# RPi-FabScan-HAT_v12.net
KiCad netlist of a schematic drawn in EAGLE
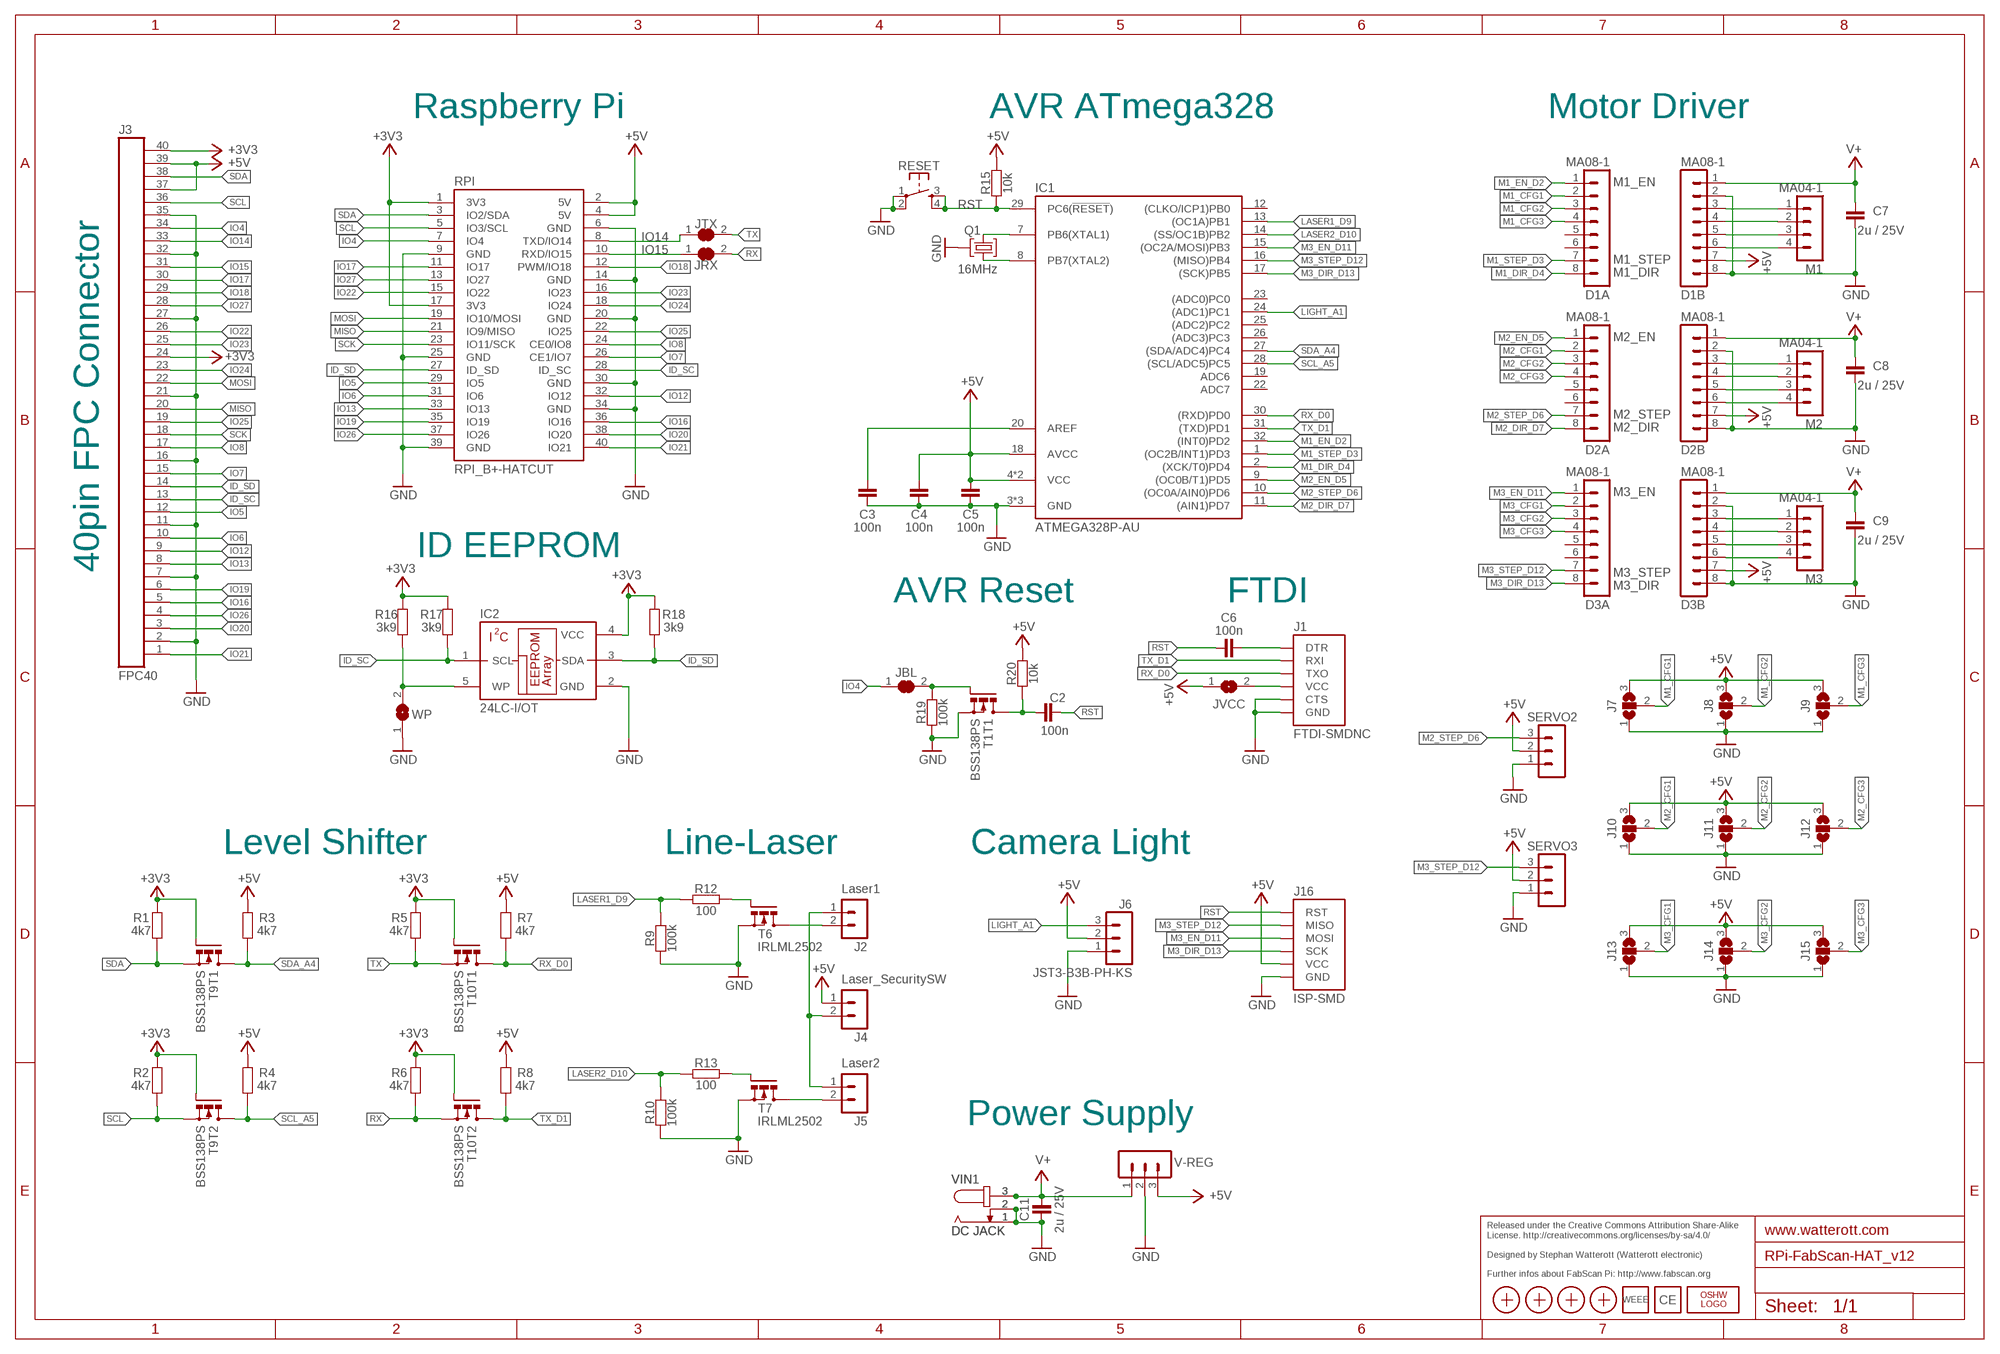
[diagram p0: schematic, sheet 1]

(export (version "E")
  (design (tool "Eeschema 10.0.6"))
  (components
    (comp (ref "1")
      (value "PASSER-07")
      (footprint "eagle-import:PASSER_07MM")
      (libsource (lib "eagle-import") (part "PASSER-07"))
    )
    (comp (ref "2")
      (value "PASSER-07")
      (footprint "eagle-import:PASSER_07MM")
      (libsource (lib "eagle-import") (part "PASSER-07"))
    )
    (comp (ref "C2")
      (value "100n")
      (footprint "eagle-import:C0402")
      (libsource (lib "eagle-import") (part "CAPACITOR-0402"))
    )
    (comp (ref "C3")
      (value "100n")
      (footprint "eagle-import:C0402")
      (libsource (lib "eagle-import") (part "CAPACITOR-0402"))
    )
    (comp (ref "C4")
      (value "100n")
      (footprint "eagle-import:C0402")
      (libsource (lib "eagle-import") (part "CAPACITOR-0402"))
    )
    (comp (ref "C5")
      (value "100n")
      (footprint "eagle-import:C0402")
      (libsource (lib "eagle-import") (part "CAPACITOR-0402"))
    )
    (comp (ref "C6")
      (value "100n")
      (footprint "eagle-import:C0402")
      (libsource (lib "eagle-import") (part "CAPACITOR-0402"))
    )
    (comp (ref "C7")
      (value "2u / 25V")
      (footprint "eagle-import:C1206")
      (libsource (lib "eagle-import") (part "CAPACITOR-1206"))
    )
    (comp (ref "C8")
      (value "2u / 25V")
      (footprint "eagle-import:C1206")
      (libsource (lib "eagle-import") (part "CAPACITOR-1206"))
    )
    (comp (ref "C9")
      (value "2u / 25V")
      (footprint "eagle-import:C1206")
      (libsource (lib "eagle-import") (part "CAPACITOR-1206"))
    )
    (comp (ref "C11")
      (value "2u / 25V")
      (footprint "eagle-import:C1206")
      (libsource (lib "eagle-import") (part "CAPACITOR-1206"))
    )
    (comp (ref "D1A")
      (value "MA08-1")
      (footprint "eagle-import:MA08-1")
      (libsource (lib "eagle-import") (part "MA08-1"))
    )
    (comp (ref "D1B")
      (value "MA08-1")
      (footprint "eagle-import:MA08-1")
      (libsource (lib "eagle-import") (part "MA08-1"))
    )
    (comp (ref "D2A")
      (value "MA08-1")
      (footprint "eagle-import:MA08-1")
      (libsource (lib "eagle-import") (part "MA08-1"))
    )
    (comp (ref "D2B")
      (value "MA08-1")
      (footprint "eagle-import:MA08-1")
      (libsource (lib "eagle-import") (part "MA08-1"))
    )
    (comp (ref "D3A")
      (value "MA08-1")
      (footprint "eagle-import:MA08-1")
      (libsource (lib "eagle-import") (part "MA08-1"))
    )
    (comp (ref "D3B")
      (value "MA08-1")
      (footprint "eagle-import:MA08-1")
      (libsource (lib "eagle-import") (part "MA08-1"))
    )
    (comp (ref "IC1")
      (value "ATMEGA328P-AU")
      (footprint "eagle-import:TQFP32")
      (libsource (lib "eagle-import") (part "ATMEGA328P-AU"))
    )
    (comp (ref "IC2")
      (value "24LC-I/OT")
      (footprint "eagle-import:SOT23-5")
      (libsource (lib "eagle-import") (part "24LC-I/OT"))
    )
    (comp (ref "J1")
      (value "FTDI-SMDNC")
      (footprint "eagle-import:FTDI_SMDNC")
      (libsource (lib "eagle-import") (part "FTDI-SMDNC"))
    )
    (comp (ref "J2")
      (value "Laser1")
      (footprint "eagle-import:MA02-1")
      (libsource (lib "eagle-import") (part "MA02-1"))
    )
    (comp (ref "J3")
      (value "FPC40")
      (footprint "eagle-import:FPC40-0.5")
      (libsource (lib "eagle-import") (part "FPC40"))
    )
    (comp (ref "J4")
      (value "Laser_SecuritySW")
      (footprint "eagle-import:MA02-1")
      (libsource (lib "eagle-import") (part "MA02-1"))
    )
    (comp (ref "J5")
      (value "Laser2")
      (footprint "eagle-import:MA02-1")
      (libsource (lib "eagle-import") (part "MA02-1"))
    )
    (comp (ref "J6")
      (value "JST3-B3B-PH-KS")
      (footprint "eagle-import:JST_B3B-PH-KS")
      (libsource (lib "eagle-import") (part "JST3-B3B-PH-KS"))
    )
    (comp (ref "J7")
      (value "JUMPER3-0603-NC")
      (footprint "eagle-import:JUMPER3-0603_NC")
      (libsource (lib "eagle-import") (part "JUMPER3-0603-NC"))
    )
    (comp (ref "J8")
      (value "JUMPER3-0603-NC")
      (footprint "eagle-import:JUMPER3-0603_NC")
      (libsource (lib "eagle-import") (part "JUMPER3-0603-NC"))
    )
    (comp (ref "J9")
      (value "JUMPER3-0603-NC")
      (footprint "eagle-import:JUMPER3-0603_NC")
      (libsource (lib "eagle-import") (part "JUMPER3-0603-NC"))
    )
    (comp (ref "J10")
      (value "JUMPER3-0603-NC")
      (footprint "eagle-import:JUMPER3-0603_NC")
      (libsource (lib "eagle-import") (part "JUMPER3-0603-NC"))
    )
    (comp (ref "J11")
      (value "JUMPER3-0603-NC")
      (footprint "eagle-import:JUMPER3-0603_NC")
      (libsource (lib "eagle-import") (part "JUMPER3-0603-NC"))
    )
    (comp (ref "J12")
      (value "JUMPER3-0603-NC")
      (footprint "eagle-import:JUMPER3-0603_NC")
      (libsource (lib "eagle-import") (part "JUMPER3-0603-NC"))
    )
    (comp (ref "J13")
      (value "JUMPER3-0603-NC")
      (footprint "eagle-import:JUMPER3-0603_NC")
      (libsource (lib "eagle-import") (part "JUMPER3-0603-NC"))
    )
    (comp (ref "J14")
      (value "JUMPER3-0603-NC")
      (footprint "eagle-import:JUMPER3-0603_NC")
      (libsource (lib "eagle-import") (part "JUMPER3-0603-NC"))
    )
    (comp (ref "J15")
      (value "JUMPER3-0603-NC")
      (footprint "eagle-import:JUMPER3-0603_NC")
      (libsource (lib "eagle-import") (part "JUMPER3-0603-NC"))
    )
    (comp (ref "J16")
      (value "ISP-SMD")
      (footprint "eagle-import:ISP-2X3_SMD")
      (libsource (lib "eagle-import") (part "ISP-SMD"))
    )
    (comp (ref "JBL")
      (value "JUMPER2-0402-NC")
      (footprint "eagle-import:JUMPER2-0402_NC")
      (libsource (lib "eagle-import") (part "JUMPER2-0402-NC"))
    )
    (comp (ref "JRX")
      (value "JUMPER2-0402-NC")
      (footprint "eagle-import:JUMPER2-0402_NC")
      (libsource (lib "eagle-import") (part "JUMPER2-0402-NC"))
    )
    (comp (ref "JTX")
      (value "JUMPER2-0402-NC")
      (footprint "eagle-import:JUMPER2-0402_NC")
      (libsource (lib "eagle-import") (part "JUMPER2-0402-NC"))
    )
    (comp (ref "JVCC")
      (value "JUMPER2-0402-NC")
      (footprint "eagle-import:JUMPER2-0402_NC")
      (libsource (lib "eagle-import") (part "JUMPER2-0402-NC"))
    )
    (comp (ref "LOGO1")
      (value "LOGO_CE-2")
      (footprint "eagle-import:CE_2MM")
      (libsource (lib "eagle-import") (part "LOGO_CE-2"))
    )
    (comp (ref "LOGO2")
      (value "OSHW_LOGOX0100")
      (footprint "eagle-import:OSHW_6X100")
      (libsource (lib "eagle-import") (part "OSHW_LOGOX0100"))
    )
    (comp (ref "LOGO3")
      (value "LOGO_WEEE-4")
      (footprint "eagle-import:WEEE_4MM")
      (libsource (lib "eagle-import") (part "LOGO_WEEE-4"))
    )
    (comp (ref "M1")
      (value "MA04-1")
      (footprint "eagle-import:MA04-1")
      (libsource (lib "eagle-import") (part "MA04-1"))
    )
    (comp (ref "M2")
      (value "MA04-1")
      (footprint "eagle-import:MA04-1")
      (libsource (lib "eagle-import") (part "MA04-1"))
    )
    (comp (ref "M3")
      (value "MA04-1")
      (footprint "eagle-import:MA04-1")
      (libsource (lib "eagle-import") (part "MA04-1"))
    )
    (comp (ref "Q1")
      (value "16MHz")
      (footprint "eagle-import:CRYSTAL_32X13")
      (libsource (lib "eagle-import") (part "CRYSTAL-RES-32"))
    )
    (comp (ref "R1")
      (value "4k7")
      (footprint "eagle-import:C0402")
      (libsource (lib "eagle-import") (part "RESISTOR-0402"))
    )
    (comp (ref "R2")
      (value "4k7")
      (footprint "eagle-import:C0402")
      (libsource (lib "eagle-import") (part "RESISTOR-0402"))
    )
    (comp (ref "R3")
      (value "4k7")
      (footprint "eagle-import:C0402")
      (libsource (lib "eagle-import") (part "RESISTOR-0402"))
    )
    (comp (ref "R4")
      (value "4k7")
      (footprint "eagle-import:C0402")
      (libsource (lib "eagle-import") (part "RESISTOR-0402"))
    )
    (comp (ref "R5")
      (value "4k7")
      (footprint "eagle-import:C0402")
      (libsource (lib "eagle-import") (part "RESISTOR-0402"))
    )
    (comp (ref "R6")
      (value "4k7")
      (footprint "eagle-import:C0402")
      (libsource (lib "eagle-import") (part "RESISTOR-0402"))
    )
    (comp (ref "R7")
      (value "4k7")
      (footprint "eagle-import:C0402")
      (libsource (lib "eagle-import") (part "RESISTOR-0402"))
    )
    (comp (ref "R8")
      (value "4k7")
      (footprint "eagle-import:C0402")
      (libsource (lib "eagle-import") (part "RESISTOR-0402"))
    )
    (comp (ref "R9")
      (value "100k")
      (footprint "eagle-import:C0402")
      (libsource (lib "eagle-import") (part "RESISTOR-0402"))
    )
    (comp (ref "R10")
      (value "100k")
      (footprint "eagle-import:C0402")
      (libsource (lib "eagle-import") (part "RESISTOR-0402"))
    )
    (comp (ref "R12")
      (value "100")
      (footprint "eagle-import:C0402")
      (libsource (lib "eagle-import") (part "RESISTOR-0402"))
    )
    (comp (ref "R13")
      (value "100")
      (footprint "eagle-import:C0402")
      (libsource (lib "eagle-import") (part "RESISTOR-0402"))
    )
    (comp (ref "R15")
      (value "10k")
      (footprint "eagle-import:C0402")
      (libsource (lib "eagle-import") (part "RESISTOR-0402"))
    )
    (comp (ref "R16")
      (value "3k9")
      (footprint "eagle-import:C0402")
      (libsource (lib "eagle-import") (part "RESISTOR-0402"))
    )
    (comp (ref "R17")
      (value "3k9")
      (footprint "eagle-import:C0402")
      (libsource (lib "eagle-import") (part "RESISTOR-0402"))
    )
    (comp (ref "R18")
      (value "3k9")
      (footprint "eagle-import:C0402")
      (libsource (lib "eagle-import") (part "RESISTOR-0402"))
    )
    (comp (ref "R19")
      (value "100k")
      (footprint "eagle-import:C0402")
      (libsource (lib "eagle-import") (part "RESISTOR-0402"))
    )
    (comp (ref "R20")
      (value "10k")
      (footprint "eagle-import:C0402")
      (libsource (lib "eagle-import") (part "RESISTOR-0402"))
    )
    (comp (ref "RESET")
      (value "SW-TACTILE-PTS840P")
      (footprint "eagle-import:SW_PTS840P")
      (libsource (lib "eagle-import") (part "SW-TACTILE-PTS840P"))
    )
    (comp (ref "RPI")
      (value "RPI_B+-HATCUT")
      (footprint "eagle-import:RPI-B+HAT_CUTOUT")
      (libsource (lib "eagle-import") (part "RPI_B+-HATCUT"))
    )
    (comp (ref "SERVO2")
      (value "MA03-1")
      (footprint "eagle-import:MA03-1")
      (libsource (lib "eagle-import") (part "MA03-1"))
    )
    (comp (ref "SERVO3")
      (value "MA03-1")
      (footprint "eagle-import:MA03-1")
      (libsource (lib "eagle-import") (part "MA03-1"))
    )
    (comp (ref "T1")
      (value "BSS138PS")
      (footprint "eagle-import:SOT363")
      (libsource (lib "eagle-import") (part "BSS138PS"))
    )
    (comp (ref "T6")
      (value "IRLML2502")
      (footprint "eagle-import:SOT23")
      (libsource (lib "eagle-import") (part "MOSFET-N-SOT23"))
    )
    (comp (ref "T7")
      (value "IRLML2502")
      (footprint "eagle-import:SOT23")
      (libsource (lib "eagle-import") (part "MOSFET-N-SOT23"))
    )
    (comp (ref "T9")
      (value "BSS138PS")
      (footprint "eagle-import:SOT363")
      (libsource (lib "eagle-import") (part "BSS138PS"))
    )
    (comp (ref "T10")
      (value "BSS138PS")
      (footprint "eagle-import:SOT363")
      (libsource (lib "eagle-import") (part "BSS138PS"))
    )
    (comp (ref "V-REG")
      (value "MA03-1")
      (footprint "eagle-import:MA03-1")
      (libsource (lib "eagle-import") (part "MA03-1"))
    )
    (comp (ref "VIN")
      (value "DC JACK")
      (footprint "eagle-import:DC-JACK")
      (libsource (lib "eagle-import") (part "DC-JACK-2.1"))
    )
    (comp (ref "VIN1")
      (value "DC JACK")
      (footprint "eagle-import:DC-JACK")
      (libsource (lib "eagle-import") (part "DC-JACK-2.1"))
    )
    (comp (ref "WP")
      (value "JUMPER2-0402-NC")
      (footprint "eagle-import:JUMPER2-0402_NC")
      (libsource (lib "eagle-import") (part "JUMPER2-0402-NC"))
    )
    (comp (ref "X1")
      (value "PASSER-07")
      (footprint "eagle-import:PASSER_07MM")
      (libsource (lib "eagle-import") (part "PASSER-07"))
    )
    (comp (ref "X4")
      (value "PASSER-07")
      (footprint "eagle-import:PASSER_07MM")
      (libsource (lib "eagle-import") (part "PASSER-07"))
    )
  )
  (nets
    (net (code "1") (name "+3V3") (class "Default")
      (node (ref "IC2") (pin "4") (pinfunction "VCC_4") (pintype "power_in"))
      (node (ref "J3") (pin "24") (pinfunction "24_24") (pintype "passive"))
      (node (ref "J3") (pin "40") (pinfunction "40_40") (pintype "passive"))
      (node (ref "R1") (pin "1") (pinfunction "1_1") (pintype "passive"))
      (node (ref "R16") (pin "2") (pinfunction "2_2") (pintype "passive"))
      (node (ref "R17") (pin "2") (pinfunction "2_2") (pintype "passive"))
      (node (ref "R18") (pin "2") (pinfunction "2_2") (pintype "passive"))
      (node (ref "R2") (pin "1") (pinfunction "1_1") (pintype "passive"))
      (node (ref "R5") (pin "1") (pinfunction "1_1") (pintype "passive"))
      (node (ref "R6") (pin "1") (pinfunction "1_1") (pintype "passive"))
      (node (ref "RPI") (pin "1") (pinfunction "3V3_1") (pintype "passive"))
      (node (ref "RPI") (pin "17") (pinfunction "3V3_17") (pintype "passive"))
      (node (ref "T10") (pin "2") (pinfunction "G_2") (pintype "passive"))
      (node (ref "T10") (pin "5") (pinfunction "G_5") (pintype "passive"))
      (node (ref "T9") (pin "2") (pinfunction "G_2") (pintype "passive"))
      (node (ref "T9") (pin "5") (pinfunction "G_5") (pintype "passive"))
    )
    (net (code "2") (name "+5V") (class "Default")
      (node (ref "C4") (pin "2") (pinfunction "2_2") (pintype "passive"))
      (node (ref "C5") (pin "2") (pinfunction "2_2") (pintype "passive"))
      (node (ref "D1B") (pin "7") (pinfunction "7_7") (pintype "passive"))
      (node (ref "D2B") (pin "7") (pinfunction "7_7") (pintype "passive"))
      (node (ref "D3B") (pin "7") (pinfunction "7_7") (pintype "passive"))
      (node (ref "IC1") (pin "18") (pinfunction "AVCC_18") (pintype "power_in"))
      (node (ref "IC1") (pin "4") (pinfunction "VCC_4") (pintype "power_in"))
      (node (ref "IC1") (pin "6") (pinfunction "VCC_6") (pintype "power_in"))
      (node (ref "J10") (pin "3") (pinfunction "3_3") (pintype "passive"))
      (node (ref "J11") (pin "3") (pinfunction "3_3") (pintype "passive"))
      (node (ref "J12") (pin "3") (pinfunction "3_3") (pintype "passive"))
      (node (ref "J13") (pin "3") (pinfunction "3_3") (pintype "passive"))
      (node (ref "J14") (pin "3") (pinfunction "3_3") (pintype "passive"))
      (node (ref "J15") (pin "3") (pinfunction "3_3") (pintype "passive"))
      (node (ref "J16") (pin "VCC") (pinfunction "VCC_VCC") (pintype "power_in"))
      (node (ref "J3") (pin "37") (pinfunction "37_37") (pintype "passive"))
      (node (ref "J3") (pin "39") (pinfunction "39_39") (pintype "passive"))
      (node (ref "J4") (pin "1") (pinfunction "1_1") (pintype "passive"))
      (node (ref "J6") (pin "2") (pinfunction "2_2") (pintype "passive"))
      (node (ref "J7") (pin "3") (pinfunction "3_3") (pintype "passive"))
      (node (ref "J8") (pin "3") (pinfunction "3_3") (pintype "passive"))
      (node (ref "J9") (pin "3") (pinfunction "3_3") (pintype "passive"))
      (node (ref "JVCC") (pin "1") (pinfunction "1_1") (pintype "passive"))
      (node (ref "R15") (pin "2") (pinfunction "2_2") (pintype "passive"))
      (node (ref "R20") (pin "2") (pinfunction "2_2") (pintype "passive"))
      (node (ref "R3") (pin "1") (pinfunction "1_1") (pintype "passive"))
      (node (ref "R4") (pin "1") (pinfunction "1_1") (pintype "passive"))
      (node (ref "R7") (pin "1") (pinfunction "1_1") (pintype "passive"))
      (node (ref "R8") (pin "1") (pinfunction "1_1") (pintype "passive"))
      (node (ref "RPI") (pin "2") (pinfunction "5V_2") (pintype "passive"))
      (node (ref "RPI") (pin "4") (pinfunction "5V_4") (pintype "passive"))
      (node (ref "SERVO2") (pin "2") (pinfunction "2_2") (pintype "passive"))
      (node (ref "SERVO3") (pin "2") (pinfunction "2_2") (pintype "passive"))
      (node (ref "V-REG") (pin "3") (pinfunction "3_3") (pintype "passive"))
    )
    (net (code "3") (name "GND") (class "Default")
      (node (ref "C11") (pin "1") (pinfunction "1_1") (pintype "passive"))
      (node (ref "C3") (pin "1") (pinfunction "1_1") (pintype "passive"))
      (node (ref "C4") (pin "1") (pinfunction "1_1") (pintype "passive"))
      (node (ref "C5") (pin "1") (pinfunction "1_1") (pintype "passive"))
      (node (ref "C7") (pin "1") (pinfunction "1_1") (pintype "passive"))
      (node (ref "C8") (pin "1") (pinfunction "1_1") (pintype "passive"))
      (node (ref "C9") (pin "1") (pinfunction "1_1") (pintype "passive"))
      (node (ref "D1B") (pin "2") (pinfunction "2_2") (pintype "passive"))
      (node (ref "D1B") (pin "8") (pinfunction "8_8") (pintype "passive"))
      (node (ref "D2B") (pin "2") (pinfunction "2_2") (pintype "passive"))
      (node (ref "D2B") (pin "8") (pinfunction "8_8") (pintype "passive"))
      (node (ref "D3B") (pin "2") (pinfunction "2_2") (pintype "passive"))
      (node (ref "D3B") (pin "8") (pinfunction "8_8") (pintype "passive"))
      (node (ref "IC1") (pin "21") (pinfunction "GND_21") (pintype "power_in"))
      (node (ref "IC1") (pin "3") (pinfunction "GND_3") (pintype "power_in"))
      (node (ref "IC1") (pin "5") (pinfunction "GND_5") (pintype "power_in"))
      (node (ref "IC2") (pin "2") (pinfunction "GND_2") (pintype "power_in"))
      (node (ref "J1") (pin "1-GND") (pinfunction "GND_1-GND") (pintype "power_in"))
      (node (ref "J1") (pin "2-CTS") (pinfunction "CTS_2-CTS") (pintype "bidirectional"))
      (node (ref "J10") (pin "1") (pinfunction "1_1") (pintype "passive"))
      (node (ref "J11") (pin "1") (pinfunction "1_1") (pintype "passive"))
      (node (ref "J12") (pin "1") (pinfunction "1_1") (pintype "passive"))
      (node (ref "J13") (pin "1") (pinfunction "1_1") (pintype "passive"))
      (node (ref "J14") (pin "1") (pinfunction "1_1") (pintype "passive"))
      (node (ref "J15") (pin "1") (pinfunction "1_1") (pintype "passive"))
      (node (ref "J16") (pin "GND") (pinfunction "GND_GND") (pintype "power_in"))
      (node (ref "J3") (pin "11") (pinfunction "11_11") (pintype "passive"))
      (node (ref "J3") (pin "16") (pinfunction "16_16") (pintype "passive"))
      (node (ref "J3") (pin "2") (pinfunction "2_2") (pintype "passive"))
      (node (ref "J3") (pin "21") (pinfunction "21_21") (pintype "passive"))
      (node (ref "J3") (pin "27") (pinfunction "27_27") (pintype "passive"))
      (node (ref "J3") (pin "32") (pinfunction "32_32") (pintype "passive"))
      (node (ref "J3") (pin "35") (pinfunction "35_35") (pintype "passive"))
      (node (ref "J3") (pin "7") (pinfunction "7_7") (pintype "passive"))
      (node (ref "J6") (pin "1") (pinfunction "1_1") (pintype "passive"))
      (node (ref "J7") (pin "1") (pinfunction "1_1") (pintype "passive"))
      (node (ref "J8") (pin "1") (pinfunction "1_1") (pintype "passive"))
      (node (ref "J9") (pin "1") (pinfunction "1_1") (pintype "passive"))
      (node (ref "Q1") (pin "GND") (pinfunction "GND_GND") (pintype "passive"))
      (node (ref "R10") (pin "1") (pinfunction "1_1") (pintype "passive"))
      (node (ref "R19") (pin "1") (pinfunction "1_1") (pintype "passive"))
      (node (ref "R9") (pin "1") (pinfunction "1_1") (pintype "passive"))
      (node (ref "RESET") (pin "1") (pinfunction "P1_1") (pintype "passive"))
      (node (ref "RESET") (pin "2") (pinfunction "P2_2") (pintype "passive"))
      (node (ref "RPI") (pin "14") (pinfunction "GND_14") (pintype "passive"))
      (node (ref "RPI") (pin "20") (pinfunction "GND_20") (pintype "passive"))
      (node (ref "RPI") (pin "25") (pinfunction "GND_25") (pintype "passive"))
      (node (ref "RPI") (pin "30") (pinfunction "GND_30") (pintype "bidirectional"))
      (node (ref "RPI") (pin "34") (pinfunction "GND_34") (pintype "bidirectional"))
      (node (ref "RPI") (pin "39") (pinfunction "GND_39") (pintype "bidirectional"))
      (node (ref "RPI") (pin "6") (pinfunction "GND_6") (pintype "passive"))
      (node (ref "RPI") (pin "9") (pinfunction "GND_9") (pintype "passive"))
      (node (ref "SERVO2") (pin "1") (pinfunction "1_1") (pintype "passive"))
      (node (ref "SERVO3") (pin "1") (pinfunction "1_1") (pintype "passive"))
      (node (ref "T1") (pin "1") (pinfunction "S_1") (pintype "passive"))
      (node (ref "T6") (pin "2") (pinfunction "S_2") (pintype "passive"))
      (node (ref "T7") (pin "2") (pinfunction "S_2") (pintype "passive"))
      (node (ref "V-REG") (pin "2") (pinfunction "2_2") (pintype "passive"))
      (node (ref "VIN") (pin "1") (pinfunction "1_1") (pintype "passive"))
      (node (ref "VIN") (pin "2") (pinfunction "2_2") (pintype "passive"))
      (node (ref "VIN1") (pin "1") (pinfunction "1_1") (pintype "passive"))
      (node (ref "VIN1") (pin "2") (pinfunction "2_2") (pintype "passive"))
      (node (ref "WP") (pin "1") (pinfunction "1_1") (pintype "passive"))
    )
    (net (code "4") (name "ID_SC") (class "Default")
      (node (ref "IC2") (pin "1") (pinfunction "SCL_1") (pintype "bidirectional"))
      (node (ref "J3") (pin "13") (pinfunction "13_13") (pintype "passive"))
      (node (ref "R17") (pin "1") (pinfunction "1_1") (pintype "passive"))
      (node (ref "RPI") (pin "28") (pinfunction "ID_SC_28") (pintype "bidirectional"))
    )
    (net (code "5") (name "ID_SD") (class "Default")
      (node (ref "IC2") (pin "3") (pinfunction "SDA_3") (pintype "bidirectional"))
      (node (ref "J3") (pin "14") (pinfunction "14_14") (pintype "passive"))
      (node (ref "R18") (pin "1") (pinfunction "1_1") (pintype "passive"))
      (node (ref "RPI") (pin "27") (pinfunction "ID_SD_27") (pintype "bidirectional"))
    )
    (net (code "6") (name "IO4") (class "Default")
      (node (ref "J3") (pin "34") (pinfunction "34_34") (pintype "passive"))
      (node (ref "JBL") (pin "1") (pinfunction "1_1") (pintype "passive"))
      (node (ref "RPI") (pin "7") (pinfunction "IO4_7") (pintype "passive"))
    )
    (net (code "7") (name "IO5") (class "Default")
      (node (ref "J3") (pin "12") (pinfunction "12_12") (pintype "passive"))
      (node (ref "RPI") (pin "29") (pinfunction "IO5_29") (pintype "bidirectional"))
    )
    (net (code "8") (name "IO6") (class "Default")
      (node (ref "J3") (pin "10") (pinfunction "10_10") (pintype "passive"))
      (node (ref "RPI") (pin "31") (pinfunction "IO6_31") (pintype "bidirectional"))
    )
    (net (code "9") (name "IO7") (class "Default")
      (node (ref "J3") (pin "15") (pinfunction "15_15") (pintype "passive"))
      (node (ref "RPI") (pin "26") (pinfunction "CE1/IO7_26") (pintype "passive"))
    )
    (net (code "10") (name "IO8") (class "Default")
      (node (ref "J3") (pin "17") (pinfunction "17_17") (pintype "passive"))
      (node (ref "RPI") (pin "24") (pinfunction "CE0/IO8_24") (pintype "passive"))
    )
    (net (code "11") (name "IO12") (class "Default")
      (node (ref "J3") (pin "9") (pinfunction "9_9") (pintype "passive"))
      (node (ref "RPI") (pin "32") (pinfunction "IO12_32") (pintype "bidirectional"))
    )
    (net (code "12") (name "IO13") (class "Default")
      (node (ref "J3") (pin "8") (pinfunction "8_8") (pintype "passive"))
      (node (ref "RPI") (pin "33") (pinfunction "IO13_33") (pintype "bidirectional"))
    )
    (net (code "13") (name "IO14") (class "Default")
      (node (ref "J3") (pin "33") (pinfunction "33_33") (pintype "passive"))
      (node (ref "JTX") (pin "1") (pinfunction "1_1") (pintype "passive"))
      (node (ref "RPI") (pin "8") (pinfunction "TXD/IO14_8") (pintype "passive"))
    )
    (net (code "14") (name "IO15") (class "Default")
      (node (ref "J3") (pin "31") (pinfunction "31_31") (pintype "passive"))
      (node (ref "JRX") (pin "1") (pinfunction "1_1") (pintype "passive"))
      (node (ref "RPI") (pin "10") (pinfunction "RXD/IO15_10") (pintype "passive"))
    )
    (net (code "15") (name "IO16") (class "Default")
      (node (ref "J3") (pin "5") (pinfunction "5_5") (pintype "passive"))
      (node (ref "RPI") (pin "36") (pinfunction "IO16_36") (pintype "bidirectional"))
    )
    (net (code "16") (name "IO17") (class "Default")
      (node (ref "J3") (pin "30") (pinfunction "30_30") (pintype "passive"))
      (node (ref "RPI") (pin "11") (pinfunction "IO17_11") (pintype "passive"))
    )
    (net (code "17") (name "IO18") (class "Default")
      (node (ref "J3") (pin "29") (pinfunction "29_29") (pintype "passive"))
      (node (ref "RPI") (pin "12") (pinfunction "PWM/IO18_12") (pintype "passive"))
    )
    (net (code "18") (name "IO19") (class "Default")
      (node (ref "J3") (pin "6") (pinfunction "6_6") (pintype "passive"))
      (node (ref "RPI") (pin "35") (pinfunction "IO19_35") (pintype "bidirectional"))
    )
    (net (code "19") (name "IO20") (class "Default")
      (node (ref "J3") (pin "3") (pinfunction "3_3") (pintype "passive"))
      (node (ref "RPI") (pin "38") (pinfunction "IO20_38") (pintype "bidirectional"))
    )
    (net (code "20") (name "IO21") (class "Default")
      (node (ref "J3") (pin "1") (pinfunction "1_1") (pintype "passive"))
      (node (ref "RPI") (pin "40") (pinfunction "IO21_40") (pintype "bidirectional"))
    )
    (net (code "21") (name "IO22") (class "Default")
      (node (ref "J3") (pin "26") (pinfunction "26_26") (pintype "passive"))
      (node (ref "RPI") (pin "15") (pinfunction "IO22_15") (pintype "passive"))
    )
    (net (code "22") (name "IO23") (class "Default")
      (node (ref "J3") (pin "25") (pinfunction "25_25") (pintype "passive"))
      (node (ref "RPI") (pin "16") (pinfunction "IO23_16") (pintype "passive"))
    )
    (net (code "23") (name "IO24") (class "Default")
      (node (ref "J3") (pin "23") (pinfunction "23_23") (pintype "passive"))
      (node (ref "RPI") (pin "18") (pinfunction "IO24_18") (pintype "passive"))
    )
    (net (code "24") (name "IO25") (class "Default")
      (node (ref "J3") (pin "19") (pinfunction "19_19") (pintype "passive"))
      (node (ref "RPI") (pin "22") (pinfunction "IO25_22") (pintype "passive"))
    )
    (net (code "25") (name "IO26") (class "Default")
      (node (ref "J3") (pin "4") (pinfunction "4_4") (pintype "passive"))
      (node (ref "RPI") (pin "37") (pinfunction "IO26_37") (pintype "bidirectional"))
    )
    (net (code "26") (name "IO27") (class "Default")
      (node (ref "J3") (pin "28") (pinfunction "28_28") (pintype "passive"))
      (node (ref "RPI") (pin "13") (pinfunction "IO27_13") (pintype "passive"))
    )
    (net (code "27") (name "LASER1_D9") (class "Default")
      (node (ref "IC1") (pin "13") (pinfunction "(OC1A)PB1_13") (pintype "bidirectional"))
      (node (ref "R12") (pin "1") (pinfunction "1_1") (pintype "passive"))
      (node (ref "R9") (pin "2") (pinfunction "2_2") (pintype "passive"))
    )
    (net (code "28") (name "LASER2_D10") (class "Default")
      (node (ref "IC1") (pin "14") (pinfunction "(SS/OC1B)PB2_14") (pintype "bidirectional"))
      (node (ref "R10") (pin "2") (pinfunction "2_2") (pintype "passive"))
      (node (ref "R13") (pin "1") (pinfunction "1_1") (pintype "passive"))
    )
    (net (code "29") (name "LIGHT_A1") (class "Default")
      (node (ref "IC1") (pin "24") (pinfunction "(ADC1)PC1_24") (pintype "bidirectional"))
      (node (ref "J6") (pin "3") (pinfunction "3_3") (pintype "passive"))
    )
    (net (code "30") (name "M1_CFG1") (class "Default")
      (node (ref "D1A") (pin "2") (pinfunction "2_2") (pintype "passive"))
      (node (ref "J7") (pin "2") (pinfunction "2_2") (pintype "passive"))
    )
    (net (code "31") (name "M1_CFG2") (class "Default")
      (node (ref "D1A") (pin "3") (pinfunction "3_3") (pintype "passive"))
      (node (ref "J8") (pin "2") (pinfunction "2_2") (pintype "passive"))
    )
    (net (code "32") (name "M1_CFG3") (class "Default")
      (node (ref "D1A") (pin "4") (pinfunction "4_4") (pintype "passive"))
      (node (ref "J9") (pin "2") (pinfunction "2_2") (pintype "passive"))
    )
    (net (code "33") (name "M1_DIR_D4") (class "Default")
      (node (ref "D1A") (pin "8") (pinfunction "8_8") (pintype "passive"))
      (node (ref "IC1") (pin "2") (pinfunction "(XCK/T0)PD4_2") (pintype "bidirectional"))
    )
    (net (code "34") (name "M1_EN_D2") (class "Default")
      (node (ref "D1A") (pin "1") (pinfunction "1_1") (pintype "passive"))
      (node (ref "IC1") (pin "32") (pinfunction "(INT0)PD2_32") (pintype "bidirectional"))
    )
    (net (code "35") (name "M1_STEP_D3") (class "Default")
      (node (ref "D1A") (pin "7") (pinfunction "7_7") (pintype "passive"))
      (node (ref "IC1") (pin "1") (pinfunction "(OC2B/INT1)PD3_1") (pintype "bidirectional"))
    )
    (net (code "36") (name "M2_CFG1") (class "Default")
      (node (ref "D2A") (pin "2") (pinfunction "2_2") (pintype "passive"))
      (node (ref "J10") (pin "2") (pinfunction "2_2") (pintype "passive"))
    )
    (net (code "37") (name "M2_CFG2") (class "Default")
      (node (ref "D2A") (pin "3") (pinfunction "3_3") (pintype "passive"))
      (node (ref "J11") (pin "2") (pinfunction "2_2") (pintype "passive"))
    )
    (net (code "38") (name "M2_CFG3") (class "Default")
      (node (ref "D2A") (pin "4") (pinfunction "4_4") (pintype "passive"))
      (node (ref "J12") (pin "2") (pinfunction "2_2") (pintype "passive"))
    )
    (net (code "39") (name "M2_DIR_D7") (class "Default")
      (node (ref "D2A") (pin "8") (pinfunction "8_8") (pintype "passive"))
      (node (ref "IC1") (pin "11") (pinfunction "(AIN1)PD7_11") (pintype "bidirectional"))
    )
    (net (code "40") (name "M2_EN_D5") (class "Default")
      (node (ref "D2A") (pin "1") (pinfunction "1_1") (pintype "passive"))
      (node (ref "IC1") (pin "9") (pinfunction "(OC0B/T1)PD5_9") (pintype "bidirectional"))
    )
    (net (code "41") (name "M2_STEP_D6") (class "Default")
      (node (ref "D2A") (pin "7") (pinfunction "7_7") (pintype "passive"))
      (node (ref "IC1") (pin "10") (pinfunction "(OC0A/AIN0)PD6_10") (pintype "bidirectional"))
      (node (ref "SERVO2") (pin "3") (pinfunction "3_3") (pintype "passive"))
    )
    (net (code "42") (name "M3_CFG1") (class "Default")
      (node (ref "D3A") (pin "2") (pinfunction "2_2") (pintype "passive"))
      (node (ref "J13") (pin "2") (pinfunction "2_2") (pintype "passive"))
    )
    (net (code "43") (name "M3_CFG2") (class "Default")
      (node (ref "D3A") (pin "3") (pinfunction "3_3") (pintype "passive"))
      (node (ref "J14") (pin "2") (pinfunction "2_2") (pintype "passive"))
    )
    (net (code "44") (name "M3_CFG3") (class "Default")
      (node (ref "D3A") (pin "4") (pinfunction "4_4") (pintype "passive"))
      (node (ref "J15") (pin "2") (pinfunction "2_2") (pintype "passive"))
    )
    (net (code "45") (name "M3_DIR_D13") (class "Default")
      (node (ref "D3A") (pin "8") (pinfunction "8_8") (pintype "passive"))
      (node (ref "IC1") (pin "17") (pinfunction "(SCK)PB5_17") (pintype "bidirectional"))
      (node (ref "J16") (pin "SCK") (pinfunction "SCK_SCK") (pintype "bidirectional"))
    )
    (net (code "46") (name "M3_EN_D11") (class "Default")
      (node (ref "D3A") (pin "1") (pinfunction "1_1") (pintype "passive"))
      (node (ref "IC1") (pin "15") (pinfunction "(OC2A/MOSI)PB3_15") (pintype "bidirectional"))
      (node (ref "J16") (pin "MOSI") (pinfunction "MOSI_MOSI") (pintype "bidirectional"))
    )
    (net (code "47") (name "M3_STEP_D12") (class "Default")
      (node (ref "D3A") (pin "7") (pinfunction "7_7") (pintype "passive"))
      (node (ref "IC1") (pin "16") (pinfunction "(MISO)PB4_16") (pintype "bidirectional"))
      (node (ref "J16") (pin "MISO") (pinfunction "MISO_MISO") (pintype "bidirectional"))
      (node (ref "SERVO3") (pin "3") (pinfunction "3_3") (pintype "passive"))
    )
    (net (code "48") (name "MISO") (class "Default")
      (node (ref "J3") (pin "20") (pinfunction "20_20") (pintype "passive"))
      (node (ref "RPI") (pin "21") (pinfunction "IO9/MISO_21") (pintype "passive"))
    )
    (net (code "49") (name "MOSI") (class "Default")
      (node (ref "J3") (pin "22") (pinfunction "22_22") (pintype "passive"))
      (node (ref "RPI") (pin "19") (pinfunction "IO10/MOSI_19") (pintype "passive"))
    )
    (net (code "50") (name "Net-(D1B-Pad3)") (class "Default")
      (node (ref "D1B") (pin "3") (pinfunction "3_3") (pintype "passive"))
      (node (ref "M1") (pin "1") (pinfunction "1_1") (pintype "passive"))
    )
    (net (code "51") (name "Net-(D1B-Pad4)") (class "Default")
      (node (ref "D1B") (pin "4") (pinfunction "4_4") (pintype "passive"))
      (node (ref "M1") (pin "2") (pinfunction "2_2") (pintype "passive"))
    )
    (net (code "52") (name "Net-(D1B-Pad5)") (class "Default")
      (node (ref "D1B") (pin "5") (pinfunction "5_5") (pintype "passive"))
      (node (ref "M1") (pin "3") (pinfunction "3_3") (pintype "passive"))
    )
    (net (code "53") (name "Net-(D1B-Pad6)") (class "Default")
      (node (ref "D1B") (pin "6") (pinfunction "6_6") (pintype "passive"))
      (node (ref "M1") (pin "4") (pinfunction "4_4") (pintype "passive"))
    )
    (net (code "54") (name "Net-(D2B-Pad3)") (class "Default")
      (node (ref "D2B") (pin "3") (pinfunction "3_3") (pintype "passive"))
      (node (ref "M2") (pin "1") (pinfunction "1_1") (pintype "passive"))
    )
    (net (code "55") (name "Net-(D2B-Pad4)") (class "Default")
      (node (ref "D2B") (pin "4") (pinfunction "4_4") (pintype "passive"))
      (node (ref "M2") (pin "2") (pinfunction "2_2") (pintype "passive"))
    )
    (net (code "56") (name "Net-(D2B-Pad5)") (class "Default")
      (node (ref "D2B") (pin "5") (pinfunction "5_5") (pintype "passive"))
      (node (ref "M2") (pin "3") (pinfunction "3_3") (pintype "passive"))
    )
    (net (code "57") (name "Net-(D2B-Pad6)") (class "Default")
      (node (ref "D2B") (pin "6") (pinfunction "6_6") (pintype "passive"))
      (node (ref "M2") (pin "4") (pinfunction "4_4") (pintype "passive"))
    )
    (net (code "58") (name "Net-(D3B-Pad3)") (class "Default")
      (node (ref "D3B") (pin "3") (pinfunction "3_3") (pintype "passive"))
      (node (ref "M3") (pin "1") (pinfunction "1_1") (pintype "passive"))
    )
    (net (code "59") (name "Net-(D3B-Pad4)") (class "Default")
      (node (ref "D3B") (pin "4") (pinfunction "4_4") (pintype "passive"))
      (node (ref "M3") (pin "2") (pinfunction "2_2") (pintype "passive"))
    )
    (net (code "60") (name "Net-(D3B-Pad5)") (class "Default")
      (node (ref "D3B") (pin "5") (pinfunction "5_5") (pintype "passive"))
      (node (ref "M3") (pin "3") (pinfunction "3_3") (pintype "passive"))
    )
    (net (code "61") (name "Net-(D3B-Pad6)") (class "Default")
      (node (ref "D3B") (pin "6") (pinfunction "6_6") (pintype "passive"))
      (node (ref "M3") (pin "4") (pinfunction "4_4") (pintype "passive"))
    )
    (net (code "62") (name "Net-(IC1-AREF)") (class "Default")
      (node (ref "C3") (pin "2") (pinfunction "2_2") (pintype "passive"))
      (node (ref "IC1") (pin "20") (pinfunction "AREF_20") (pintype "passive"))
    )
    (net (code "63") (name "Net-(IC1-PB6(XTAL1))") (class "Default")
      (node (ref "IC1") (pin "7") (pinfunction "PB6(XTAL1)_7") (pintype "bidirectional"))
      (node (ref "Q1") (pin "2") (pinfunction "2_2") (pintype "passive"))
    )
    (net (code "64") (name "Net-(IC1-PB7(XTAL2))") (class "Default")
      (node (ref "IC1") (pin "8") (pinfunction "PB7(XTAL2)_8") (pintype "bidirectional"))
      (node (ref "Q1") (pin "1") (pinfunction "1_1") (pintype "passive"))
    )
    (net (code "65") (name "Net-(IC2-WP)") (class "Default")
      (node (ref "IC2") (pin "5") (pinfunction "WP_5") (pintype "bidirectional"))
      (node (ref "R16") (pin "1") (pinfunction "1_1") (pintype "passive"))
      (node (ref "WP") (pin "2") (pinfunction "2_2") (pintype "passive"))
    )
    (net (code "66") (name "Net-(J1-DTR)") (class "Default")
      (node (ref "C6") (pin "1") (pinfunction "1_1") (pintype "passive"))
      (node (ref "J1") (pin "6-DTR") (pinfunction "DTR_6-DTR") (pintype "bidirectional"))
    )
    (net (code "67") (name "Net-(J1-VCC)") (class "Default")
      (node (ref "J1") (pin "3-VCC") (pinfunction "VCC_3-VCC") (pintype "power_in"))
      (node (ref "JVCC") (pin "2") (pinfunction "2_2") (pintype "passive"))
    )
    (net (code "68") (name "Net-(J2-Pad1)") (class "Default")
      (node (ref "J2") (pin "1") (pinfunction "1_1") (pintype "passive"))
      (node (ref "J4") (pin "2") (pinfunction "2_2") (pintype "passive"))
      (node (ref "J5") (pin "1") (pinfunction "1_1") (pintype "passive"))
    )
    (net (code "69") (name "Net-(T1A-D)") (class "Default")
      (node (ref "C2") (pin "2") (pinfunction "2_2") (pintype "passive"))
      (node (ref "R20") (pin "1") (pinfunction "1_1") (pintype "passive"))
      (node (ref "T1") (pin "6") (pinfunction "D_6") (pintype "passive"))
    )
    (net (code "70") (name "Net-(T1A-G)") (class "Default")
      (node (ref "JBL") (pin "2") (pinfunction "2_2") (pintype "passive"))
      (node (ref "R19") (pin "2") (pinfunction "2_2") (pintype "passive"))
      (node (ref "T1") (pin "2") (pinfunction "G_2") (pintype "passive"))
    )
    (net (code "71") (name "Net-(T6-D)") (class "Default")
      (node (ref "J2") (pin "2") (pinfunction "2_2") (pintype "passive"))
      (node (ref "T6") (pin "3") (pinfunction "D_3") (pintype "passive"))
    )
    (net (code "72") (name "Net-(T6-G)") (class "Default")
      (node (ref "R12") (pin "2") (pinfunction "2_2") (pintype "passive"))
      (node (ref "T6") (pin "1") (pinfunction "G_1") (pintype "passive"))
    )
    (net (code "73") (name "Net-(T7-D)") (class "Default")
      (node (ref "J5") (pin "2") (pinfunction "2_2") (pintype "passive"))
      (node (ref "T7") (pin "3") (pinfunction "D_3") (pintype "passive"))
    )
    (net (code "74") (name "Net-(T7-G)") (class "Default")
      (node (ref "R13") (pin "2") (pinfunction "2_2") (pintype "passive"))
      (node (ref "T7") (pin "1") (pinfunction "G_1") (pintype "passive"))
    )
    (net (code "75") (name "RST") (class "Default")
      (node (ref "C2") (pin "1") (pinfunction "1_1") (pintype "passive"))
      (node (ref "C6") (pin "2") (pinfunction "2_2") (pintype "passive"))
      (node (ref "IC1") (pin "29") (pinfunction "PC6(~{RESET})_29") (pintype "bidirectional"))
      (node (ref "J16") (pin "RST") (pinfunction "RST_RST") (pintype "bidirectional"))
      (node (ref "R15") (pin "1") (pinfunction "1_1") (pintype "passive"))
      (node (ref "RESET") (pin "3") (pinfunction "S1_3") (pintype "passive"))
      (node (ref "RESET") (pin "4") (pinfunction "S2_4") (pintype "passive"))
    )
    (net (code "76") (name "RX") (class "Default")
      (node (ref "JRX") (pin "2") (pinfunction "2_2") (pintype "passive"))
      (node (ref "R6") (pin "2") (pinfunction "2_2") (pintype "passive"))
      (node (ref "T10") (pin "4") (pinfunction "S_4") (pintype "passive"))
    )
    (net (code "77") (name "RX_D0") (class "Default")
      (node (ref "IC1") (pin "30") (pinfunction "(RXD)PD0_30") (pintype "bidirectional"))
      (node (ref "J1") (pin "4-TXO") (pinfunction "TXO_4-TXO") (pintype "bidirectional"))
      (node (ref "R7") (pin "2") (pinfunction "2_2") (pintype "passive"))
      (node (ref "T10") (pin "6") (pinfunction "D_6") (pintype "passive"))
    )
    (net (code "78") (name "SCK") (class "Default")
      (node (ref "J3") (pin "18") (pinfunction "18_18") (pintype "passive"))
      (node (ref "RPI") (pin "23") (pinfunction "IO11/SCK_23") (pintype "passive"))
    )
    (net (code "79") (name "SCL") (class "Default")
      (node (ref "J3") (pin "36") (pinfunction "36_36") (pintype "passive"))
      (node (ref "R2") (pin "2") (pinfunction "2_2") (pintype "passive"))
      (node (ref "RPI") (pin "5") (pinfunction "IO3/SCL_5") (pintype "passive"))
      (node (ref "T9") (pin "4") (pinfunction "S_4") (pintype "passive"))
    )
    (net (code "80") (name "SCL_A5") (class "Default")
      (node (ref "IC1") (pin "28") (pinfunction "(SCL/ADC5)PC5_28") (pintype "bidirectional"))
      (node (ref "R4") (pin "2") (pinfunction "2_2") (pintype "passive"))
      (node (ref "T9") (pin "3") (pinfunction "D_3") (pintype "passive"))
    )
    (net (code "81") (name "SDA") (class "Default")
      (node (ref "J3") (pin "38") (pinfunction "38_38") (pintype "passive"))
      (node (ref "R1") (pin "2") (pinfunction "2_2") (pintype "passive"))
      (node (ref "RPI") (pin "3") (pinfunction "IO2/SDA_3") (pintype "passive"))
      (node (ref "T9") (pin "1") (pinfunction "S_1") (pintype "passive"))
    )
    (net (code "82") (name "SDA_A4") (class "Default")
      (node (ref "IC1") (pin "27") (pinfunction "(SDA/ADC4)PC4_27") (pintype "bidirectional"))
      (node (ref "R3") (pin "2") (pinfunction "2_2") (pintype "passive"))
      (node (ref "T9") (pin "6") (pinfunction "D_6") (pintype "passive"))
    )
    (net (code "83") (name "TX") (class "Default")
      (node (ref "JTX") (pin "2") (pinfunction "2_2") (pintype "passive"))
      (node (ref "R5") (pin "2") (pinfunction "2_2") (pintype "passive"))
      (node (ref "T10") (pin "1") (pinfunction "S_1") (pintype "passive"))
    )
    (net (code "84") (name "TX_D1") (class "Default")
      (node (ref "IC1") (pin "31") (pinfunction "(TXD)PD1_31") (pintype "bidirectional"))
      (node (ref "J1") (pin "5-RXI") (pinfunction "RXI_5-RXI") (pintype "bidirectional"))
      (node (ref "R8") (pin "2") (pinfunction "2_2") (pintype "passive"))
      (node (ref "T10") (pin "3") (pinfunction "D_3") (pintype "passive"))
    )
    (net (code "85") (name "V+") (class "Default")
      (node (ref "C11") (pin "2") (pinfunction "2_2") (pintype "passive"))
      (node (ref "C7") (pin "2") (pinfunction "2_2") (pintype "passive"))
      (node (ref "C8") (pin "2") (pinfunction "2_2") (pintype "passive"))
      (node (ref "C9") (pin "2") (pinfunction "2_2") (pintype "passive"))
      (node (ref "D1B") (pin "1") (pinfunction "1_1") (pintype "passive"))
      (node (ref "D2B") (pin "1") (pinfunction "1_1") (pintype "passive"))
      (node (ref "D3B") (pin "1") (pinfunction "1_1") (pintype "passive"))
      (node (ref "V-REG") (pin "1") (pinfunction "1_1") (pintype "passive"))
      (node (ref "VIN") (pin "3") (pinfunction "3_3") (pintype "passive"))
      (node (ref "VIN1") (pin "3") (pinfunction "3_3") (pintype "passive"))
    )
    (net (code "86") (name "unconnected-(D1A-Pad5)") (class "Default")
      (node (ref "D1A") (pin "5") (pinfunction "5_5") (pintype "passive"))
    )
    (net (code "87") (name "unconnected-(D1A-Pad6)") (class "Default")
      (node (ref "D1A") (pin "6") (pinfunction "6_6") (pintype "passive"))
    )
    (net (code "88") (name "unconnected-(D2A-Pad5)") (class "Default")
      (node (ref "D2A") (pin "5") (pinfunction "5_5") (pintype "passive"))
    )
    (net (code "89") (name "unconnected-(D2A-Pad6)") (class "Default")
      (node (ref "D2A") (pin "6") (pinfunction "6_6") (pintype "passive"))
    )
    (net (code "90") (name "unconnected-(D3A-Pad5)") (class "Default")
      (node (ref "D3A") (pin "5") (pinfunction "5_5") (pintype "passive"))
    )
    (net (code "91") (name "unconnected-(D3A-Pad6)") (class "Default")
      (node (ref "D3A") (pin "6") (pinfunction "6_6") (pintype "passive"))
    )
    (net (code "92") (name "unconnected-(IC1-(ADC0)PC0-Pad23)") (class "Default")
      (node (ref "IC1") (pin "23") (pinfunction "(ADC0)PC0_23") (pintype "bidirectional"))
    )
    (net (code "93") (name "unconnected-(IC1-(ADC2)PC2-Pad25)") (class "Default")
      (node (ref "IC1") (pin "25") (pinfunction "(ADC2)PC2_25") (pintype "bidirectional"))
    )
    (net (code "94") (name "unconnected-(IC1-(ADC3)PC3-Pad26)") (class "Default")
      (node (ref "IC1") (pin "26") (pinfunction "(ADC3)PC3_26") (pintype "bidirectional"))
    )
    (net (code "95") (name "unconnected-(IC1-(CLKO{slash}ICP1)PB0-Pad12)") (class "Default")
      (node (ref "IC1") (pin "12") (pinfunction "(CLKO/ICP1)PB0_12") (pintype "bidirectional"))
    )
    (net (code "96") (name "unconnected-(IC1-ADC6-Pad19)") (class "Default")
      (node (ref "IC1") (pin "19") (pinfunction "ADC6_19") (pintype "bidirectional"))
    )
    (net (code "97") (name "unconnected-(IC1-ADC7-Pad22)") (class "Default")
      (node (ref "IC1") (pin "22") (pinfunction "ADC7_22") (pintype "bidirectional"))
    )
  )
)
